# Triggers.net
KiCad netlist of a schematic drawn in Altium Designer
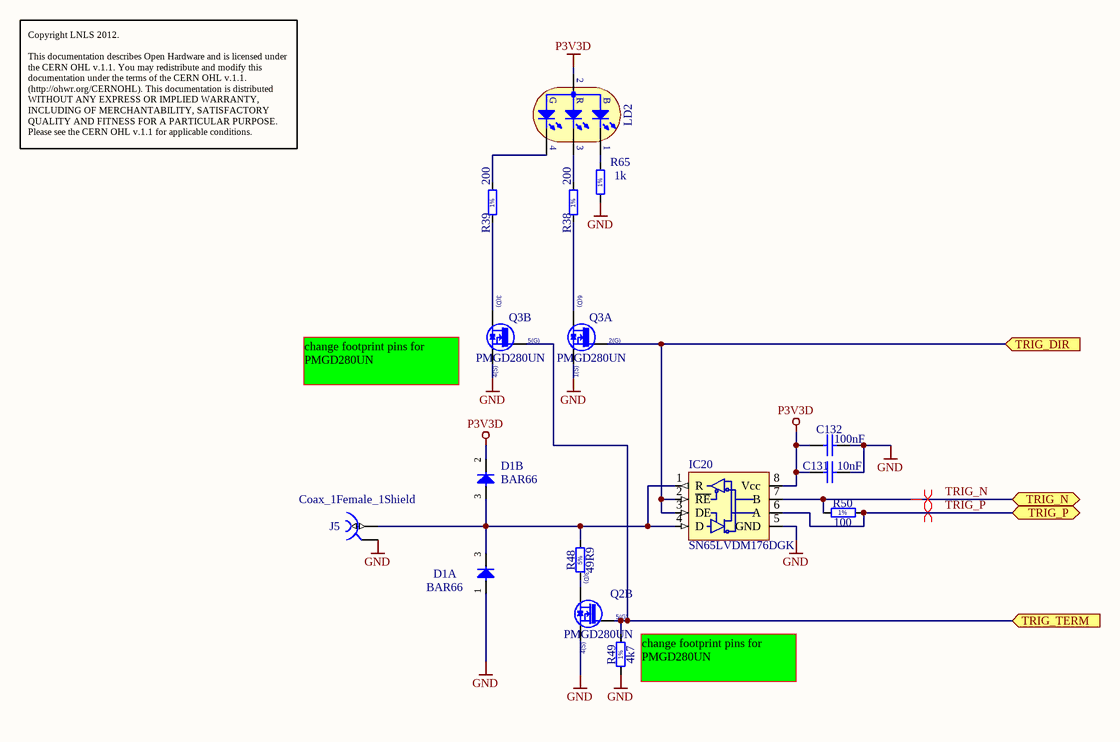
[diagram p0: Triggers.SchDoc]

(export (version "E")
  (design (tool "Eeschema 10.0.6"))
  (components
    (comp (ref "C131")
      (value "10nF")
      (footprint "CAPC0603X33N")
      (description "Non-polarised capacitor")
      (fields
        (field (name "PART NUMBER") "CC0201_10NF_10V_10%_X5R")
        (field (name "VOLTAGE") "10V")
        (field (name "AUTHOR") "CERN DEM JLC")
      )
      (libsource (lib "Capacitors") (part "Capacitor - non polarized"))
    )
    (comp (ref "C132")
      (value "100nF")
      (footprint "CAPC0603X33N")
      (description "Non-polarised capacitor")
      (fields
        (field (name "PART NUMBER") "CC0201_100NF_6.3V_10%_X5R")
        (field (name "VOLTAGE") "6.3V")
        (field (name "AUTHOR") "CERN DEM JLC")
      )
      (libsource (lib "Capacitors") (part "Capacitor - non polarized"))
    )
    (comp (ref "D1")
      (value "BAR66")
      (footprint "SOT95P240X110-3I")
      (description "Serial Diode")
      (fields
        (field (name "VOLTAGE") "150V")
        (field (name "POWER") "250mA")
        (field (name "AUTHOR") "CERN DEM JLC")
      )
      (libsource (lib "EDA-02408-V1") (part "Diode x2 A1C3_A3C2"))
    )
    (comp (ref "IC20")
      (value "SN65LVDM176DGK")
      (footprint "SOP65P490X110-8N")
      (description "Differential Bus Transceiver")
      (fields (field (name "MANUFACTURER") "TEXAS INSTRUMENTS") (field (name "AUTHOR") "LNLS DIG GBMB"))
      (libsource (lib "ICs And Semiconductors") (part "5176"))
    )
    (comp (ref "J5")
      (value "Coax_1Female_1Shield")
      (footprint "HUBER-SUHNER_85_MMCX-50-0-1/111 OH")
      (fields
        (field (name "PART NUMBER") "HUBER-SUHNER_85_MMCX-50-0-1/111 OH")
        (field (name "MANUFACTURER") "HUBER+SUHNER")
        (field (name "MANUFACTURER PART NUMBER") "85_MMCX-50-0-1/111 OH")
        (field (name "AUTHOR") "CERN DEM JLC")
      )
      (libsource (lib "Connectors") (part "Coax_1Female_1Shield"))
    )
    (comp (ref "LD2")
      (value "~")
      (footprint "LED_AVAGO_HSMF-C113")
      (description "Tricolor LEDs 1 Cathode Blue, 2 Common Anode, 3 Cathode Red, 4 Cathode Green")
      (fields
        (field (name "PART NUMBER") "LED_AVAGO_HSMF-C113")
        (field (name "MANUFACTURER") "AVAGO TECHNOLOGIES")
        (field (name "AUTHOR") "CERN DEM JLC")
      )
      (libsource (lib "ICs And Semiconductors") (part "LED Blue-Red-Green 1CB_2AC_3CR_4CG"))
    )
    (comp (ref "Q2")
      (value "PMGD280UN")
      (footprint "SOT65P210X110-6N")
      (description "Dual N-Channel micro TrenchMOS™ Ultra Low Level FET")
      (fields (field (name "MANUFACTURER") "NXP SEMICONDUCTORS") (field (name "AUTHOR") "CERN DEM JLC"))
      (libsource (lib "ICs And Semiconductors") (part "PMGD280UN"))
    )
    (comp (ref "Q3")
      (value "PMGD280UN")
      (footprint "SOT65P210X110-6N")
      (description "Dual N-Channel micro TrenchMOS™ Ultra Low Level FET")
      (fields (field (name "MANUFACTURER") "NXP SEMICONDUCTORS") (field (name "AUTHOR") "CERN DEM JLC"))
      (libsource (lib "ICs And Semiconductors") (part "PMGD280UN"))
    )
    (comp (ref "R38")
      (value "200")
      (footprint "RESC1005X40N")
      (description "Resistor - 1%")
      (fields
        (field (name "PART NUMBER") "R0402_200R_1%_0.0625W_100PPM")
        (field (name "POWER") "0.0625W")
        (field (name "AUTHOR") "CERN DEM JLC")
      )
      (libsource (lib "Resistors") (part "Resistor - 1%"))
    )
    (comp (ref "R39")
      (value "200")
      (footprint "RESC1005X40N")
      (description "Resistor - 1%")
      (fields
        (field (name "PART NUMBER") "R0402_200R_1%_0.0625W_100PPM")
        (field (name "POWER") "0.0625W")
        (field (name "AUTHOR") "CERN DEM JLC")
      )
      (libsource (lib "Resistors") (part "Resistor - 1%"))
    )
    (comp (ref "R48")
      (value "49R9")
      (footprint "RESC3225X70N")
      (description "Resistor - 5%")
      (fields
        (field (name "PART NUMBER") "R1210_49R9_1%_0.33W_100PPM")
        (field (name "POWER") "0.33W")
        (field (name "AUTHOR") "CERN DEM JLC")
      )
      (libsource (lib "Resistors") (part "Resistor - 5%"))
    )
    (comp (ref "R49")
      (value "4k7")
      (footprint "RESC1005X40N")
      (description "Resistor - 1%")
      (fields
        (field (name "PART NUMBER") "R0402_4K7_1%_0.0625W_100PPM")
        (field (name "POWER") "0.0625W")
        (field (name "AUTHOR") "CERN DEM JLC")
      )
      (libsource (lib "Resistors") (part "Resistor - 1%"))
    )
    (comp (ref "R50")
      (value "100")
      (footprint "RESC1005X40N")
      (description "Resistor - 1%")
      (fields
        (field (name "PART NUMBER") "R0402_100R_1%_0.0625W_100PPM")
        (field (name "POWER") "0.0625W")
        (field (name "AUTHOR") "CERN DEM JLC")
      )
      (libsource (lib "Resistors") (part "Resistor - 1%"))
    )
    (comp (ref "R65")
      (value "1k")
      (footprint "RESC1005X40N")
      (description "Resistor - 1%")
      (fields
        (field (name "PART NUMBER") "R0402_1K_1%_0.0625W_100PPM")
        (field (name "POWER") "0.0625W")
        (field (name "AUTHOR") "CERN DEM JLC")
      )
      (libsource (lib "Resistors") (part "Resistor - 1%"))
    )
  )
  (nets
    (net (code "1") (name "/TRIG_DIR") (class "Default")
      (node (ref "IC20") (pin "2") (pinfunction "~{RE}_2") (pintype "input"))
      (node (ref "IC20") (pin "3") (pinfunction "DE_3") (pintype "input"))
      (node (ref "Q3") (pin "2") (pinfunction "G_2") (pintype "passive"))
    )
    (net (code "2") (name "/TRIG_N") (class "Default")
      (node (ref "IC20") (pin "7") (pinfunction "B_7") (pintype "bidirectional"))
      (node (ref "R50") (pin "1") (pinfunction "1_1") (pintype "passive"))
    )
    (net (code "3") (name "/TRIG_P") (class "Default")
      (node (ref "IC20") (pin "6") (pinfunction "A_6") (pintype "bidirectional"))
      (node (ref "R50") (pin "2") (pinfunction "2_2") (pintype "passive"))
    )
    (net (code "4") (name "/TRIG_TERM") (class "Default")
      (node (ref "Q2") (pin "5") (pinfunction "G_5") (pintype "passive"))
      (node (ref "Q3") (pin "5") (pinfunction "G_5") (pintype "passive"))
      (node (ref "R49") (pin "2") (pinfunction "2_2") (pintype "passive"))
    )
    (net (code "5") (name "GND") (class "Default")
      (node (ref "C131") (pin "2") (pinfunction "2_2") (pintype "passive"))
      (node (ref "C132") (pin "2") (pinfunction "2_2") (pintype "passive"))
      (node (ref "D1") (pin "1") (pinfunction "A_1") (pintype "passive"))
      (node (ref "IC20") (pin "5") (pinfunction "GND_5") (pintype "power_in"))
      (node (ref "J5") (pin "2") (pinfunction "2_2") (pintype "passive"))
      (node (ref "Q2") (pin "4") (pinfunction "S_4") (pintype "passive"))
      (node (ref "Q3") (pin "1") (pinfunction "S_1") (pintype "passive"))
      (node (ref "Q3") (pin "4") (pinfunction "S_4") (pintype "passive"))
      (node (ref "R49") (pin "1") (pinfunction "1_1") (pintype "passive"))
      (node (ref "R65") (pin "1") (pinfunction "1_1") (pintype "passive"))
    )
    (net (code "6") (name "Net-(D1A-COMAC)") (class "Default")
      (node (ref "D1") (pin "3") (pinfunction "COMAC_3") (pintype "passive"))
      (node (ref "IC20") (pin "1") (pinfunction "R_1") (pintype "output"))
      (node (ref "IC20") (pin "4") (pinfunction "D_4") (pintype "input"))
      (node (ref "J5") (pin "1") (pinfunction "1_1") (pintype "bidirectional"))
      (node (ref "R48") (pin "2") (pinfunction "2_2") (pintype "passive"))
    )
    (net (code "7") (name "Net-(LD2-CB)") (class "Default")
      (node (ref "LD2") (pin "1") (pinfunction "CB_1") (pintype "passive"))
      (node (ref "R65") (pin "2") (pinfunction "2_2") (pintype "passive"))
    )
    (net (code "8") (name "Net-(LD2-CG)") (class "Default")
      (node (ref "LD2") (pin "4") (pinfunction "CG_4") (pintype "passive"))
      (node (ref "R39") (pin "2") (pinfunction "2_2") (pintype "passive"))
    )
    (net (code "9") (name "Net-(LD2-CR)") (class "Default")
      (node (ref "LD2") (pin "3") (pinfunction "CR_3") (pintype "passive"))
      (node (ref "R38") (pin "2") (pinfunction "2_2") (pintype "passive"))
    )
    (net (code "10") (name "Net-(Q2B-D)") (class "Default")
      (node (ref "Q2") (pin "3") (pinfunction "D_3") (pintype "passive"))
      (node (ref "R48") (pin "1") (pinfunction "1_1") (pintype "passive"))
    )
    (net (code "11") (name "Net-(Q3A-D)") (class "Default")
      (node (ref "Q3") (pin "6") (pinfunction "D_6") (pintype "passive"))
      (node (ref "R38") (pin "1") (pinfunction "1_1") (pintype "passive"))
    )
    (net (code "12") (name "Net-(Q3B-D)") (class "Default")
      (node (ref "Q3") (pin "3") (pinfunction "D_3") (pintype "passive"))
      (node (ref "R39") (pin "1") (pinfunction "1_1") (pintype "passive"))
    )
    (net (code "13") (name "P3V3D") (class "Default")
      (node (ref "C131") (pin "1") (pinfunction "1_1") (pintype "passive"))
      (node (ref "C132") (pin "1") (pinfunction "1_1") (pintype "passive"))
      (node (ref "D1") (pin "2") (pinfunction "C_2") (pintype "passive"))
      (node (ref "IC20") (pin "8") (pinfunction "Vcc_8") (pintype "power_in"))
      (node (ref "LD2") (pin "2") (pinfunction "AC_2") (pintype "passive"))
    )
  )
)
